# PT08.net
KiCad netlist of a schematic drawn in EAGLE
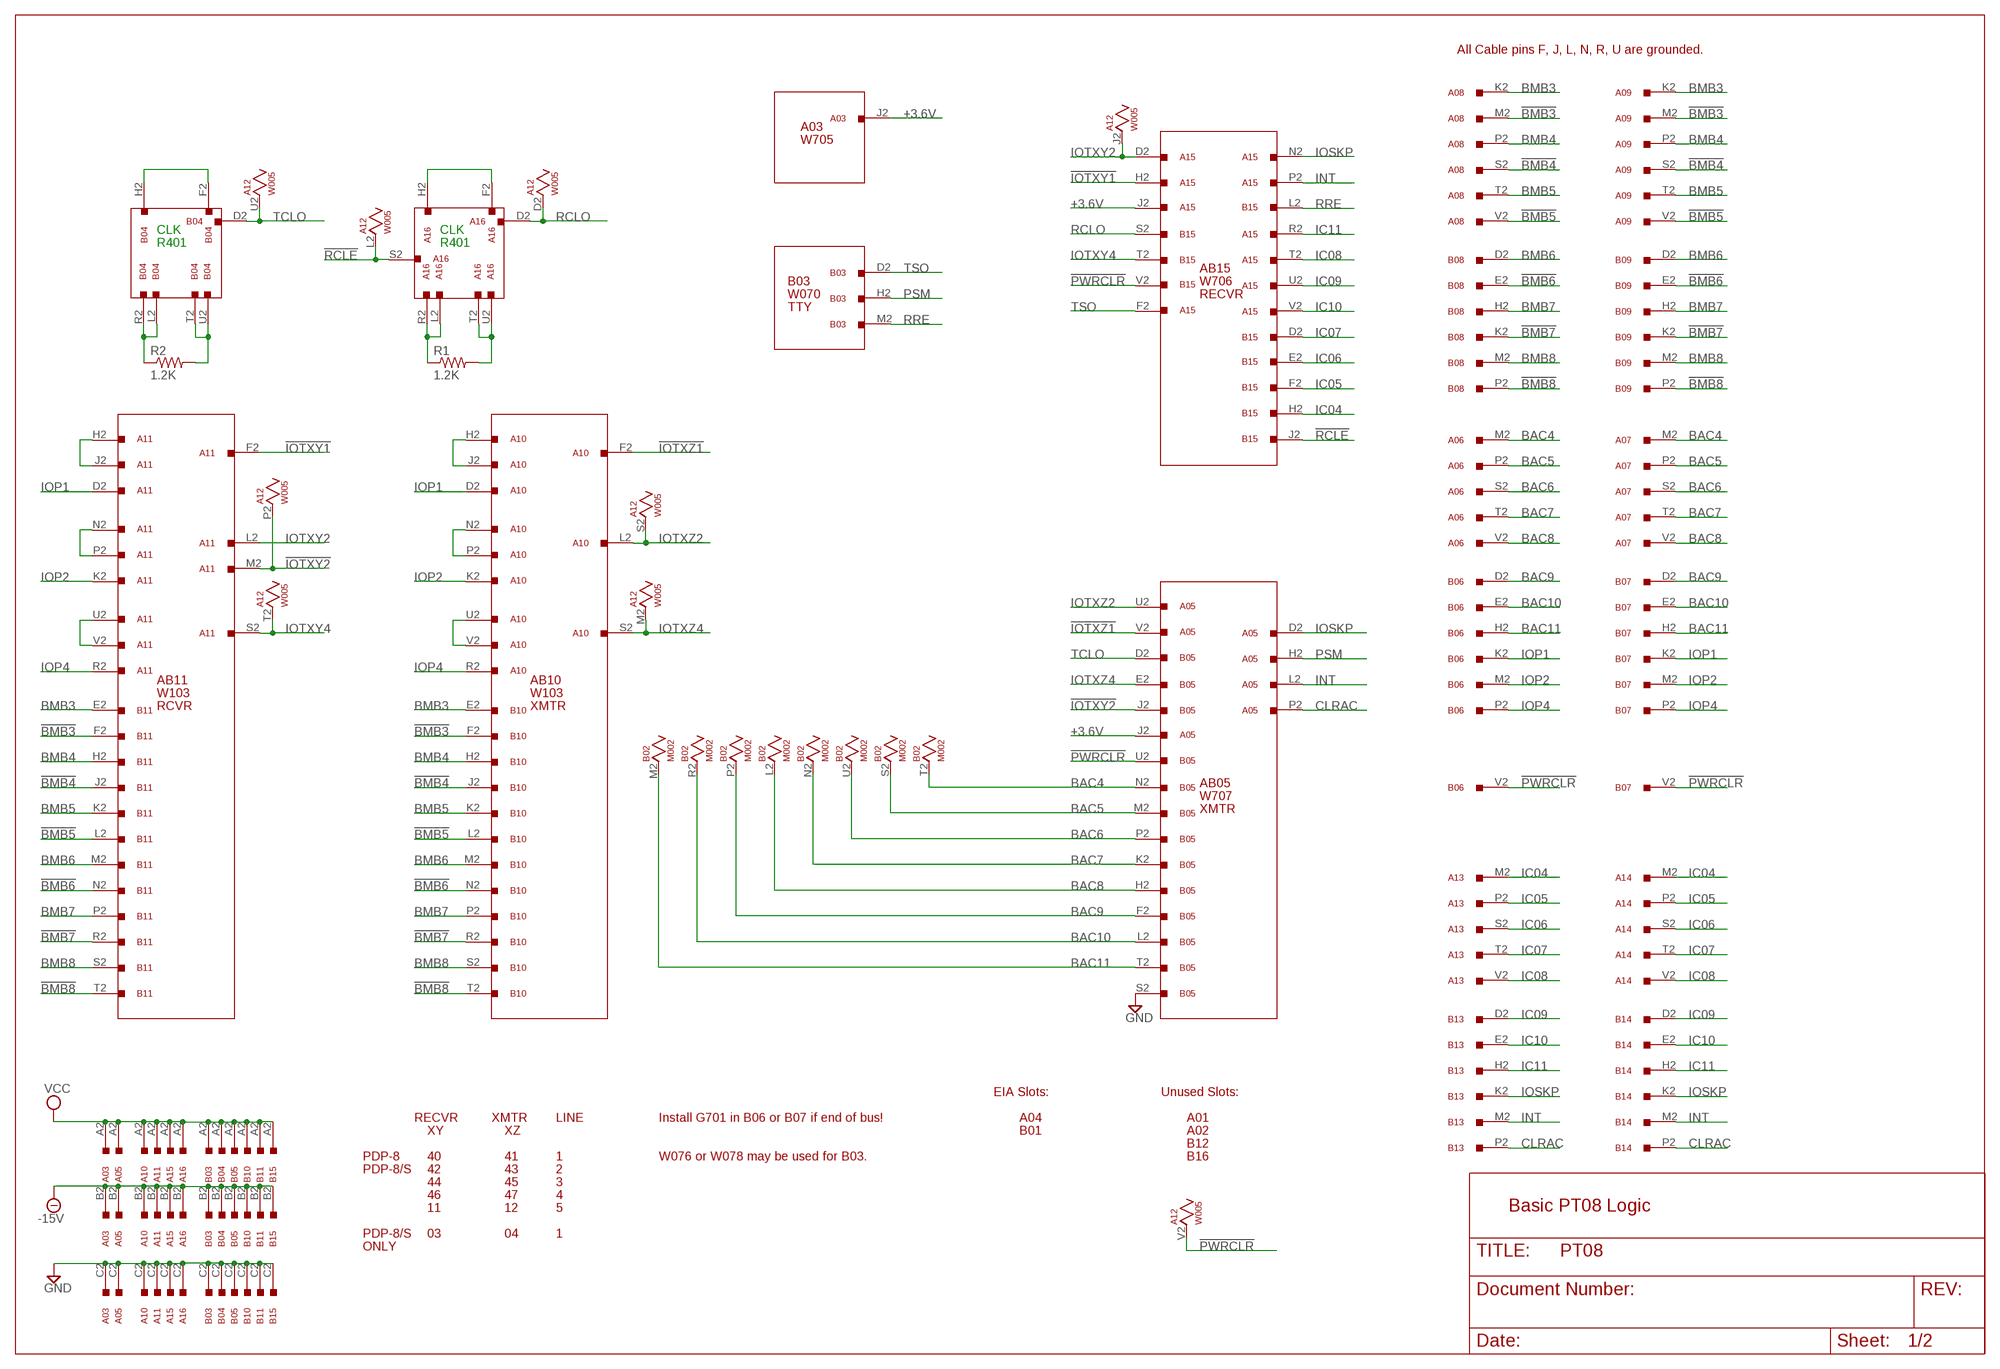
[diagram p0: schematic, sheet 1]
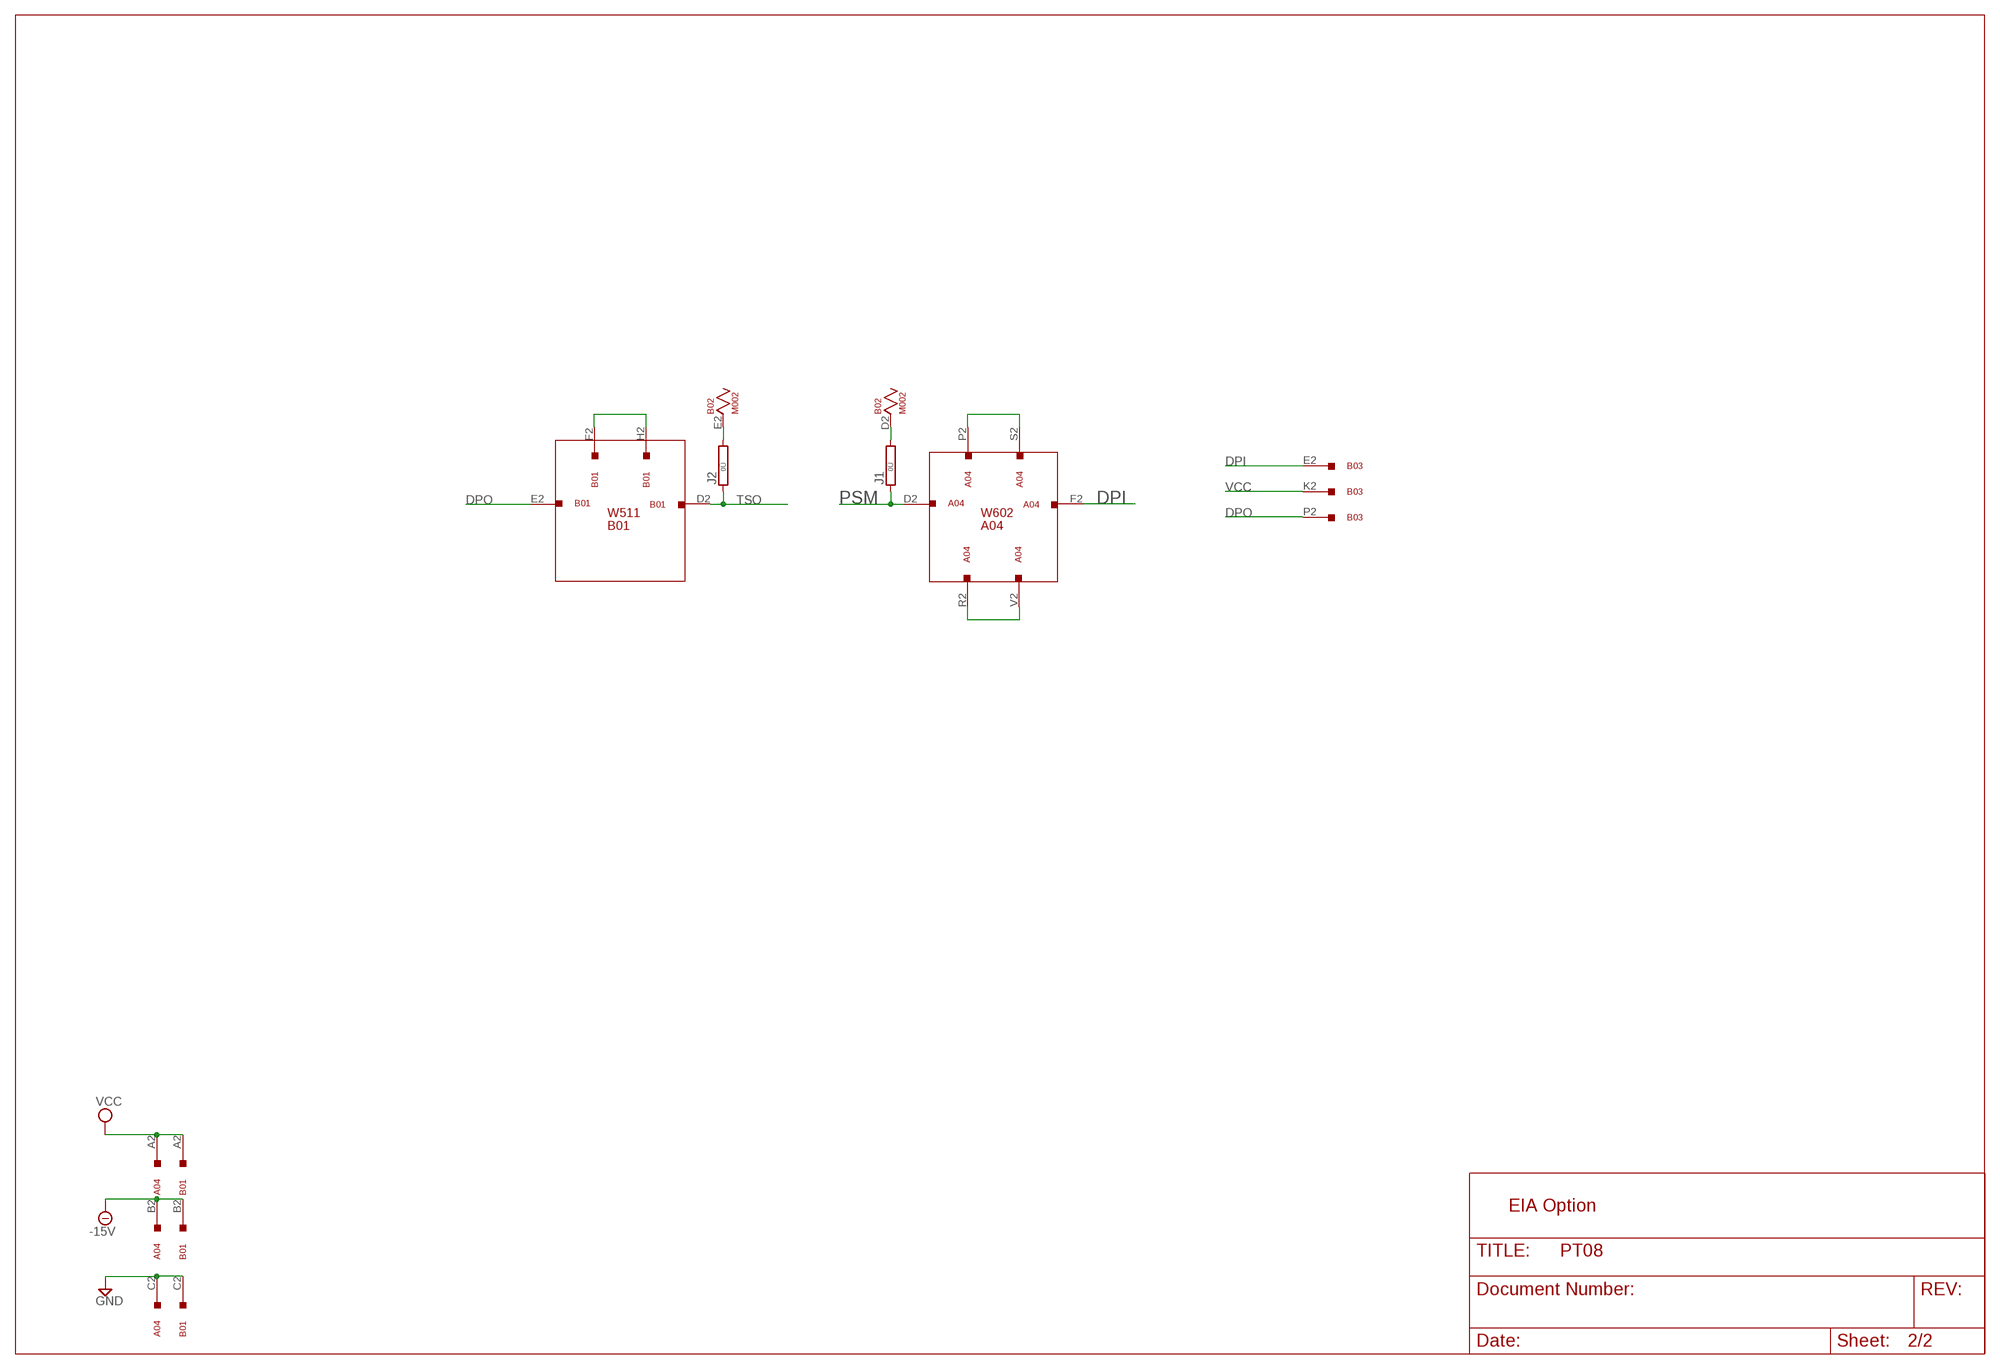
[diagram p1: schematic, sheet 2]

(export (version "E")
  (design (tool "Eeschema 10.0.6"))
  (components
    (comp (ref "A01")
      (value "H807")
      (footprint "eagle-import:H807")
      (libsource (lib "eagle-import") (part "H807"))
    )
    (comp (ref "A02")
      (value "H807")
      (footprint "eagle-import:H807")
      (libsource (lib "eagle-import") (part "H807"))
    )
    (comp (ref "A03")
      (value "W705")
      (footprint "eagle-import:H807")
      (libsource (lib "eagle-import") (part "W023"))
    )
    (comp (ref "A05")
      (value "W707")
      (footprint "eagle-import:H807")
      (libsource (lib "eagle-import") (part "W023"))
    )
    (comp (ref "A06")
      (value "W011")
      (footprint "eagle-import:H807")
      (libsource (lib "eagle-import") (part "W011"))
    )
    (comp (ref "A07")
      (value "W011")
      (footprint "eagle-import:H807")
      (libsource (lib "eagle-import") (part "W011"))
    )
    (comp (ref "A08")
      (value "W011")
      (footprint "eagle-import:H807")
      (libsource (lib "eagle-import") (part "W011"))
    )
    (comp (ref "A09")
      (value "W011")
      (footprint "eagle-import:H807")
      (libsource (lib "eagle-import") (part "W011"))
    )
    (comp (ref "A10")
      (value "W103")
      (footprint "eagle-import:H807")
      (libsource (lib "eagle-import") (part "W023"))
    )
    (comp (ref "A11")
      (value "W103")
      (footprint "eagle-import:H807")
      (libsource (lib "eagle-import") (part "W023"))
    )
    (comp (ref "A12")
      (value "W005")
      (footprint "eagle-import:H807")
      (libsource (lib "eagle-import") (part "W005"))
    )
    (comp (ref "A13")
      (value "W011")
      (footprint "eagle-import:H807")
      (libsource (lib "eagle-import") (part "W011"))
    )
    (comp (ref "A14")
      (value "W011")
      (footprint "eagle-import:H807")
      (libsource (lib "eagle-import") (part "W011"))
    )
    (comp (ref "A15")
      (value "W706")
      (footprint "eagle-import:H807")
      (libsource (lib "eagle-import") (part "W023"))
    )
    (comp (ref "A16")
      (value "R401")
      (footprint "eagle-import:H807")
      (libsource (lib "eagle-import") (part "W023"))
    )
    (comp (ref "B02")
      (value "M002")
      (footprint "eagle-import:H807")
      (libsource (lib "eagle-import") (part "M002"))
    )
    (comp (ref "B03")
      (value "W076")
      (footprint "eagle-import:H807")
      (libsource (lib "eagle-import") (part "W023"))
    )
    (comp (ref "B04")
      (value "R401")
      (footprint "eagle-import:H807")
      (libsource (lib "eagle-import") (part "W023"))
    )
    (comp (ref "B05")
      (value "W707")
      (footprint "eagle-import:H807")
      (libsource (lib "eagle-import") (part "W023"))
    )
    (comp (ref "B06")
      (value "W011")
      (footprint "eagle-import:H807")
      (libsource (lib "eagle-import") (part "W011"))
    )
    (comp (ref "B07")
      (value "W011")
      (footprint "eagle-import:H807")
      (libsource (lib "eagle-import") (part "W011"))
    )
    (comp (ref "B08")
      (value "W011")
      (footprint "eagle-import:H807")
      (libsource (lib "eagle-import") (part "W011"))
    )
    (comp (ref "B09")
      (value "W011")
      (footprint "eagle-import:H807")
      (libsource (lib "eagle-import") (part "W011"))
    )
    (comp (ref "B10")
      (value "W103")
      (footprint "eagle-import:H807")
      (libsource (lib "eagle-import") (part "W023"))
    )
    (comp (ref "B11")
      (value "W103")
      (footprint "eagle-import:H807")
      (libsource (lib "eagle-import") (part "W023"))
    )
    (comp (ref "B12")
      (value "H807")
      (footprint "eagle-import:H807")
      (libsource (lib "eagle-import") (part "H807"))
    )
    (comp (ref "B13")
      (value "W011")
      (footprint "eagle-import:H807")
      (libsource (lib "eagle-import") (part "W011"))
    )
    (comp (ref "B14")
      (value "W011")
      (footprint "eagle-import:H807")
      (libsource (lib "eagle-import") (part "W011"))
    )
    (comp (ref "B15")
      (value "W706")
      (footprint "eagle-import:H807")
      (libsource (lib "eagle-import") (part "W023"))
    )
    (comp (ref "B16")
      (value "H807")
      (footprint "eagle-import:H807")
      (libsource (lib "eagle-import") (part "H807"))
    )
    (comp (ref "R1")
      (value "1.2K")
      (footprint "eagle-import:0207_10")
      (libsource (lib "eagle-import") (part "R-US_0207/10"))
    )
    (comp (ref "R2")
      (value "1.2K")
      (footprint "eagle-import:0207_10")
      (libsource (lib "eagle-import") (part "R-US_0207/10"))
    )
    (comp (ref "A04")
      (value "W602")
      (footprint "eagle-import:H807")
      (libsource (lib "eagle-import") (part "W023"))
    )
    (comp (ref "B01")
      (value "W511")
      (footprint "eagle-import:H807")
      (libsource (lib "eagle-import") (part "W023"))
    )
    (comp (ref "J1")
      (value "0R")
      (footprint "eagle-import:0R_10")
      (libsource (lib "eagle-import") (part "0R"))
    )
    (comp (ref "J2")
      (value "0R")
      (footprint "eagle-import:0R_10")
      (libsource (lib "eagle-import") (part "0R"))
    )
  )
  (nets
    (net (code "1") (name "+3.6V") (class "Default")
      (node (ref "A03") (pin "J2") (pinfunction "P$2_J2") (pintype "bidirectional"))
      (node (ref "A05") (pin "J2") (pinfunction "P$2_J2") (pintype "bidirectional"))
      (node (ref "A15") (pin "J2") (pinfunction "P$2_J2") (pintype "bidirectional"))
    )
    (net (code "2") (name "-15V") (class "Default")
      (node (ref "A03") (pin "B2") (pinfunction "P$2_B2") (pintype "bidirectional"))
      (node (ref "A04") (pin "B2") (pinfunction "P$2_B2") (pintype "bidirectional"))
      (node (ref "A05") (pin "B2") (pinfunction "P$2_B2") (pintype "bidirectional"))
      (node (ref "A10") (pin "B2") (pinfunction "P$2_B2") (pintype "bidirectional"))
      (node (ref "A11") (pin "B2") (pinfunction "P$2_B2") (pintype "bidirectional"))
      (node (ref "A15") (pin "B2") (pinfunction "P$2_B2") (pintype "bidirectional"))
      (node (ref "A16") (pin "B2") (pinfunction "P$2_B2") (pintype "bidirectional"))
      (node (ref "B01") (pin "B2") (pinfunction "P$2_B2") (pintype "bidirectional"))
      (node (ref "B03") (pin "B2") (pinfunction "P$2_B2") (pintype "bidirectional"))
      (node (ref "B04") (pin "B2") (pinfunction "P$2_B2") (pintype "bidirectional"))
      (node (ref "B05") (pin "B2") (pinfunction "P$2_B2") (pintype "bidirectional"))
      (node (ref "B10") (pin "B2") (pinfunction "P$2_B2") (pintype "bidirectional"))
      (node (ref "B11") (pin "B2") (pinfunction "P$2_B2") (pintype "bidirectional"))
      (node (ref "B15") (pin "B2") (pinfunction "P$2_B2") (pintype "bidirectional"))
    )
    (net (code "3") (name "BAC4") (class "Default")
      (node (ref "A06") (pin "M2") (pinfunction "P$2_M2") (pintype "bidirectional"))
      (node (ref "A07") (pin "M2") (pinfunction "P$2_M2") (pintype "bidirectional"))
      (node (ref "B02") (pin "T2") (pinfunction "P$1_T2") (pintype "passive"))
      (node (ref "B05") (pin "N2") (pinfunction "P$2_N2") (pintype "bidirectional"))
    )
    (net (code "4") (name "BAC5") (class "Default")
      (node (ref "A06") (pin "P2") (pinfunction "P$2_P2") (pintype "bidirectional"))
      (node (ref "A07") (pin "P2") (pinfunction "P$2_P2") (pintype "bidirectional"))
      (node (ref "B02") (pin "S2") (pinfunction "P$1_S2") (pintype "passive"))
      (node (ref "B05") (pin "M2") (pinfunction "P$2_M2") (pintype "bidirectional"))
    )
    (net (code "5") (name "BAC6") (class "Default")
      (node (ref "A06") (pin "S2") (pinfunction "P$2_S2") (pintype "bidirectional"))
      (node (ref "A07") (pin "S2") (pinfunction "P$2_S2") (pintype "bidirectional"))
      (node (ref "B02") (pin "U2") (pinfunction "P$1_U2") (pintype "passive"))
      (node (ref "B05") (pin "P2") (pinfunction "P$2_P2") (pintype "bidirectional"))
    )
    (net (code "6") (name "BAC7") (class "Default")
      (node (ref "A06") (pin "T2") (pinfunction "P$2_T2") (pintype "bidirectional"))
      (node (ref "A07") (pin "T2") (pinfunction "P$2_T2") (pintype "bidirectional"))
      (node (ref "B02") (pin "N2") (pinfunction "P$1_N2") (pintype "passive"))
      (node (ref "B05") (pin "K2") (pinfunction "P$2_K2") (pintype "bidirectional"))
    )
    (net (code "7") (name "BAC8") (class "Default")
      (node (ref "A06") (pin "V2") (pinfunction "P$2_V2") (pintype "bidirectional"))
      (node (ref "A07") (pin "V2") (pinfunction "P$2_V2") (pintype "bidirectional"))
      (node (ref "B02") (pin "L2") (pinfunction "P$1_L2") (pintype "passive"))
      (node (ref "B05") (pin "H2") (pinfunction "P$2_H2") (pintype "bidirectional"))
    )
    (net (code "8") (name "BAC9") (class "Default")
      (node (ref "B02") (pin "P2") (pinfunction "P$1_P2") (pintype "passive"))
      (node (ref "B05") (pin "F2") (pinfunction "P$2_F2") (pintype "bidirectional"))
      (node (ref "B06") (pin "D2") (pinfunction "P$2_D2") (pintype "bidirectional"))
      (node (ref "B07") (pin "D2") (pinfunction "P$2_D2") (pintype "bidirectional"))
    )
    (net (code "9") (name "BAC10") (class "Default")
      (node (ref "B02") (pin "R2") (pinfunction "P$1_R2") (pintype "passive"))
      (node (ref "B05") (pin "L2") (pinfunction "P$2_L2") (pintype "bidirectional"))
      (node (ref "B06") (pin "E2") (pinfunction "P$2_E2") (pintype "bidirectional"))
      (node (ref "B07") (pin "E2") (pinfunction "P$2_E2") (pintype "bidirectional"))
    )
    (net (code "10") (name "BAC11") (class "Default")
      (node (ref "B02") (pin "M2") (pinfunction "P$1_M2") (pintype "passive"))
      (node (ref "B05") (pin "T2") (pinfunction "P$2_T2") (pintype "bidirectional"))
      (node (ref "B06") (pin "H2") (pinfunction "P$2_H2") (pintype "bidirectional"))
      (node (ref "B07") (pin "H2") (pinfunction "P$2_H2") (pintype "bidirectional"))
    )
    (net (code "11") (name "BMB3") (class "Default")
      (node (ref "A08") (pin "K2") (pinfunction "P$2_K2") (pintype "bidirectional"))
      (node (ref "A09") (pin "K2") (pinfunction "P$2_K2") (pintype "bidirectional"))
      (node (ref "B10") (pin "E2") (pinfunction "P$2_E2") (pintype "bidirectional"))
      (node (ref "B11") (pin "E2") (pinfunction "P$2_E2") (pintype "bidirectional"))
    )
    (net (code "12") (name "BMB4") (class "Default")
      (node (ref "A08") (pin "P2") (pinfunction "P$2_P2") (pintype "bidirectional"))
      (node (ref "A09") (pin "P2") (pinfunction "P$2_P2") (pintype "bidirectional"))
      (node (ref "B10") (pin "H2") (pinfunction "P$2_H2") (pintype "bidirectional"))
      (node (ref "B11") (pin "H2") (pinfunction "P$2_H2") (pintype "bidirectional"))
    )
    (net (code "13") (name "BMB5") (class "Default")
      (node (ref "A08") (pin "T2") (pinfunction "P$2_T2") (pintype "bidirectional"))
      (node (ref "A09") (pin "T2") (pinfunction "P$2_T2") (pintype "bidirectional"))
      (node (ref "B10") (pin "K2") (pinfunction "P$2_K2") (pintype "bidirectional"))
      (node (ref "B11") (pin "K2") (pinfunction "P$2_K2") (pintype "bidirectional"))
    )
    (net (code "14") (name "BMB6") (class "Default")
      (node (ref "B08") (pin "D2") (pinfunction "P$2_D2") (pintype "bidirectional"))
      (node (ref "B09") (pin "D2") (pinfunction "P$2_D2") (pintype "bidirectional"))
      (node (ref "B10") (pin "M2") (pinfunction "P$2_M2") (pintype "bidirectional"))
      (node (ref "B11") (pin "M2") (pinfunction "P$2_M2") (pintype "bidirectional"))
    )
    (net (code "15") (name "BMB7") (class "Default")
      (node (ref "B08") (pin "H2") (pinfunction "P$2_H2") (pintype "bidirectional"))
      (node (ref "B09") (pin "H2") (pinfunction "P$2_H2") (pintype "bidirectional"))
      (node (ref "B10") (pin "P2") (pinfunction "P$2_P2") (pintype "bidirectional"))
      (node (ref "B11") (pin "P2") (pinfunction "P$2_P2") (pintype "bidirectional"))
    )
    (net (code "16") (name "BMB8") (class "Default")
      (node (ref "B08") (pin "M2") (pinfunction "P$2_M2") (pintype "bidirectional"))
      (node (ref "B09") (pin "M2") (pinfunction "P$2_M2") (pintype "bidirectional"))
      (node (ref "B10") (pin "S2") (pinfunction "P$2_S2") (pintype "bidirectional"))
      (node (ref "B11") (pin "S2") (pinfunction "P$2_S2") (pintype "bidirectional"))
    )
    (net (code "17") (name "CLRAC") (class "Default")
      (node (ref "A05") (pin "P2") (pinfunction "P$2_P2") (pintype "bidirectional"))
      (node (ref "B13") (pin "P2") (pinfunction "P$2_P2") (pintype "bidirectional"))
      (node (ref "B14") (pin "P2") (pinfunction "P$2_P2") (pintype "bidirectional"))
    )
    (net (code "18") (name "DPI") (class "Default")
      (node (ref "A04") (pin "F2") (pinfunction "P$2_F2") (pintype "bidirectional"))
      (node (ref "B03") (pin "E2") (pinfunction "P$2_E2") (pintype "bidirectional"))
    )
    (net (code "19") (name "DPO") (class "Default")
      (node (ref "B01") (pin "E2") (pinfunction "P$2_E2") (pintype "bidirectional"))
      (node (ref "B03") (pin "P2") (pinfunction "P$2_P2") (pintype "bidirectional"))
    )
    (net (code "20") (name "GND") (class "Default")
      (node (ref "A03") (pin "C2") (pinfunction "P$2_C2") (pintype "bidirectional"))
      (node (ref "A04") (pin "C2") (pinfunction "P$2_C2") (pintype "bidirectional"))
      (node (ref "A05") (pin "C2") (pinfunction "P$2_C2") (pintype "bidirectional"))
      (node (ref "A10") (pin "C2") (pinfunction "P$2_C2") (pintype "bidirectional"))
      (node (ref "A11") (pin "C2") (pinfunction "P$2_C2") (pintype "bidirectional"))
      (node (ref "A15") (pin "C2") (pinfunction "P$2_C2") (pintype "bidirectional"))
      (node (ref "A16") (pin "C2") (pinfunction "P$2_C2") (pintype "bidirectional"))
      (node (ref "B01") (pin "C2") (pinfunction "P$2_C2") (pintype "bidirectional"))
      (node (ref "B03") (pin "C2") (pinfunction "P$2_C2") (pintype "bidirectional"))
      (node (ref "B04") (pin "C2") (pinfunction "P$2_C2") (pintype "bidirectional"))
      (node (ref "B05") (pin "C2") (pinfunction "P$2_C2") (pintype "bidirectional"))
      (node (ref "B05") (pin "S2") (pinfunction "P$2_S2") (pintype "bidirectional"))
      (node (ref "B10") (pin "C2") (pinfunction "P$2_C2") (pintype "bidirectional"))
      (node (ref "B11") (pin "C2") (pinfunction "P$2_C2") (pintype "bidirectional"))
      (node (ref "B15") (pin "C2") (pinfunction "P$2_C2") (pintype "bidirectional"))
    )
    (net (code "21") (name "IC04") (class "Default")
      (node (ref "A13") (pin "M2") (pinfunction "P$2_M2") (pintype "bidirectional"))
      (node (ref "A14") (pin "M2") (pinfunction "P$2_M2") (pintype "bidirectional"))
      (node (ref "B15") (pin "H2") (pinfunction "P$2_H2") (pintype "bidirectional"))
    )
    (net (code "22") (name "IC05") (class "Default")
      (node (ref "A13") (pin "P2") (pinfunction "P$2_P2") (pintype "bidirectional"))
      (node (ref "A14") (pin "P2") (pinfunction "P$2_P2") (pintype "bidirectional"))
      (node (ref "B15") (pin "F2") (pinfunction "P$2_F2") (pintype "bidirectional"))
    )
    (net (code "23") (name "IC06") (class "Default")
      (node (ref "A13") (pin "S2") (pinfunction "P$2_S2") (pintype "bidirectional"))
      (node (ref "A14") (pin "S2") (pinfunction "P$2_S2") (pintype "bidirectional"))
      (node (ref "B15") (pin "E2") (pinfunction "P$2_E2") (pintype "bidirectional"))
    )
    (net (code "24") (name "IC07") (class "Default")
      (node (ref "A13") (pin "T2") (pinfunction "P$2_T2") (pintype "bidirectional"))
      (node (ref "A14") (pin "T2") (pinfunction "P$2_T2") (pintype "bidirectional"))
      (node (ref "B15") (pin "D2") (pinfunction "P$2_D2") (pintype "bidirectional"))
    )
    (net (code "25") (name "IC08") (class "Default")
      (node (ref "A13") (pin "V2") (pinfunction "P$2_V2") (pintype "bidirectional"))
      (node (ref "A14") (pin "V2") (pinfunction "P$2_V2") (pintype "bidirectional"))
      (node (ref "A15") (pin "T2") (pinfunction "P$2_T2") (pintype "bidirectional"))
    )
    (net (code "26") (name "IC09") (class "Default")
      (node (ref "A15") (pin "U2") (pinfunction "P$2_U2") (pintype "bidirectional"))
      (node (ref "B13") (pin "D2") (pinfunction "P$2_D2") (pintype "bidirectional"))
      (node (ref "B14") (pin "D2") (pinfunction "P$2_D2") (pintype "bidirectional"))
    )
    (net (code "27") (name "IC10") (class "Default")
      (node (ref "A15") (pin "V2") (pinfunction "P$2_V2") (pintype "bidirectional"))
      (node (ref "B13") (pin "E2") (pinfunction "P$2_E2") (pintype "bidirectional"))
      (node (ref "B14") (pin "E2") (pinfunction "P$2_E2") (pintype "bidirectional"))
    )
    (net (code "28") (name "IC11") (class "Default")
      (node (ref "A15") (pin "R2") (pinfunction "P$2_R2") (pintype "bidirectional"))
      (node (ref "B13") (pin "H2") (pinfunction "P$2_H2") (pintype "bidirectional"))
      (node (ref "B14") (pin "H2") (pinfunction "P$2_H2") (pintype "bidirectional"))
    )
    (net (code "29") (name "INT") (class "Default")
      (node (ref "A05") (pin "L2") (pinfunction "P$2_L2") (pintype "bidirectional"))
      (node (ref "A15") (pin "P2") (pinfunction "P$2_P2") (pintype "bidirectional"))
      (node (ref "B13") (pin "M2") (pinfunction "P$2_M2") (pintype "bidirectional"))
      (node (ref "B14") (pin "M2") (pinfunction "P$2_M2") (pintype "bidirectional"))
    )
    (net (code "30") (name "IOP1") (class "Default")
      (node (ref "A10") (pin "D2") (pinfunction "P$2_D2") (pintype "bidirectional"))
      (node (ref "A11") (pin "D2") (pinfunction "P$2_D2") (pintype "bidirectional"))
      (node (ref "B06") (pin "K2") (pinfunction "P$2_K2") (pintype "bidirectional"))
      (node (ref "B07") (pin "K2") (pinfunction "P$2_K2") (pintype "bidirectional"))
    )
    (net (code "31") (name "IOP2") (class "Default")
      (node (ref "A10") (pin "K2") (pinfunction "P$2_K2") (pintype "bidirectional"))
      (node (ref "A11") (pin "K2") (pinfunction "P$2_K2") (pintype "bidirectional"))
      (node (ref "B06") (pin "M2") (pinfunction "P$2_M2") (pintype "bidirectional"))
      (node (ref "B07") (pin "M2") (pinfunction "P$2_M2") (pintype "bidirectional"))
    )
    (net (code "32") (name "IOP4") (class "Default")
      (node (ref "A10") (pin "R2") (pinfunction "P$2_R2") (pintype "bidirectional"))
      (node (ref "A11") (pin "R2") (pinfunction "P$2_R2") (pintype "bidirectional"))
      (node (ref "B06") (pin "P2") (pinfunction "P$2_P2") (pintype "bidirectional"))
      (node (ref "B07") (pin "P2") (pinfunction "P$2_P2") (pintype "bidirectional"))
    )
    (net (code "33") (name "IOSKP") (class "Default")
      (node (ref "A05") (pin "D2") (pinfunction "P$2_D2") (pintype "bidirectional"))
      (node (ref "A15") (pin "N2") (pinfunction "P$2_N2") (pintype "bidirectional"))
      (node (ref "B13") (pin "K2") (pinfunction "P$2_K2") (pintype "bidirectional"))
      (node (ref "B14") (pin "K2") (pinfunction "P$2_K2") (pintype "bidirectional"))
    )
    (net (code "34") (name "IOTXY2") (class "Default")
      (node (ref "A11") (pin "L2") (pinfunction "P$2_L2") (pintype "bidirectional"))
      (node (ref "A12") (pin "J2") (pinfunction "P$1_J2") (pintype "passive"))
      (node (ref "A15") (pin "D2") (pinfunction "P$2_D2") (pintype "bidirectional"))
    )
    (net (code "35") (name "IOTXY4") (class "Default")
      (node (ref "A11") (pin "S2") (pinfunction "P$2_S2") (pintype "bidirectional"))
      (node (ref "A12") (pin "T2") (pinfunction "P$1_T2") (pintype "passive"))
      (node (ref "B15") (pin "T2") (pinfunction "P$2_T2") (pintype "bidirectional"))
    )
    (net (code "36") (name "IOTXZ2") (class "Default")
      (node (ref "A05") (pin "U2") (pinfunction "P$2_U2") (pintype "bidirectional"))
      (node (ref "A10") (pin "L2") (pinfunction "P$2_L2") (pintype "bidirectional"))
      (node (ref "A12") (pin "S2") (pinfunction "P$1_S2") (pintype "passive"))
    )
    (net (code "37") (name "IOTXZ4") (class "Default")
      (node (ref "A10") (pin "S2") (pinfunction "P$2_S2") (pintype "bidirectional"))
      (node (ref "A12") (pin "M2") (pinfunction "P$1_M2") (pintype "passive"))
      (node (ref "B05") (pin "E2") (pinfunction "P$2_E2") (pintype "bidirectional"))
    )
    (net (code "38") (name "Net-(A04M-P$2)") (class "Default")
      (node (ref "A04") (pin "P2") (pinfunction "P$2_P2") (pintype "bidirectional"))
      (node (ref "A04") (pin "S2") (pinfunction "P$2_S2") (pintype "bidirectional"))
    )
    (net (code "39") (name "Net-(A04N-P$2)") (class "Default")
      (node (ref "A04") (pin "R2") (pinfunction "P$2_R2") (pintype "bidirectional"))
      (node (ref "A04") (pin "V2") (pinfunction "P$2_V2") (pintype "bidirectional"))
    )
    (net (code "40") (name "Net-(A10G-P$2)") (class "Default")
      (node (ref "A10") (pin "H2") (pinfunction "P$2_H2") (pintype "bidirectional"))
      (node (ref "A10") (pin "J2") (pinfunction "P$2_J2") (pintype "bidirectional"))
    )
    (net (code "41") (name "Net-(A10L-P$2)") (class "Default")
      (node (ref "A10") (pin "N2") (pinfunction "P$2_N2") (pintype "bidirectional"))
      (node (ref "A10") (pin "P2") (pinfunction "P$2_P2") (pintype "bidirectional"))
    )
    (net (code "42") (name "Net-(A10Q-P$2)") (class "Default")
      (node (ref "A10") (pin "U2") (pinfunction "P$2_U2") (pintype "bidirectional"))
      (node (ref "A10") (pin "V2") (pinfunction "P$2_V2") (pintype "bidirectional"))
    )
    (net (code "43") (name "Net-(A11G-P$2)") (class "Default")
      (node (ref "A11") (pin "H2") (pinfunction "P$2_H2") (pintype "bidirectional"))
      (node (ref "A11") (pin "J2") (pinfunction "P$2_J2") (pintype "bidirectional"))
    )
    (net (code "44") (name "Net-(A11L-P$2)") (class "Default")
      (node (ref "A11") (pin "N2") (pinfunction "P$2_N2") (pintype "bidirectional"))
      (node (ref "A11") (pin "P2") (pinfunction "P$2_P2") (pintype "bidirectional"))
    )
    (net (code "45") (name "Net-(A11Q-P$2)") (class "Default")
      (node (ref "A11") (pin "U2") (pinfunction "P$2_U2") (pintype "bidirectional"))
      (node (ref "A11") (pin "V2") (pinfunction "P$2_V2") (pintype "bidirectional"))
    )
    (net (code "46") (name "Net-(A16F-P$2)") (class "Default")
      (node (ref "A16") (pin "F2") (pinfunction "P$2_F2") (pintype "bidirectional"))
      (node (ref "A16") (pin "H2") (pinfunction "P$2_H2") (pintype "bidirectional"))
    )
    (net (code "47") (name "Net-(A16J-P$2)") (class "Default")
      (node (ref "A16") (pin "L2") (pinfunction "P$2_L2") (pintype "bidirectional"))
      (node (ref "A16") (pin "R2") (pinfunction "P$2_R2") (pintype "bidirectional"))
      (node (ref "R1") (pin "1") (pinfunction "1_1") (pintype "passive"))
    )
    (net (code "48") (name "Net-(A16P-P$2)") (class "Default")
      (node (ref "A16") (pin "T2") (pinfunction "P$2_T2") (pintype "bidirectional"))
      (node (ref "A16") (pin "U2") (pinfunction "P$2_U2") (pintype "bidirectional"))
      (node (ref "R1") (pin "2") (pinfunction "2_2") (pintype "passive"))
    )
    (net (code "49") (name "Net-(B01F-P$2)") (class "Default")
      (node (ref "B01") (pin "F2") (pinfunction "P$2_F2") (pintype "bidirectional"))
      (node (ref "B01") (pin "H2") (pinfunction "P$2_H2") (pintype "bidirectional"))
    )
    (net (code "50") (name "Net-(B02A-P$1)") (class "Default")
      (node (ref "B02") (pin "D2") (pinfunction "P$1_D2") (pintype "passive"))
      (node (ref "J1") (pin "2") (pinfunction "2_2") (pintype "passive"))
    )
    (net (code "51") (name "Net-(B02B-P$1)") (class "Default")
      (node (ref "B02") (pin "E2") (pinfunction "P$1_E2") (pintype "passive"))
      (node (ref "J2") (pin "2") (pinfunction "2_2") (pintype "passive"))
    )
    (net (code "52") (name "Net-(B04F-P$2)") (class "Default")
      (node (ref "B04") (pin "F2") (pinfunction "P$2_F2") (pintype "bidirectional"))
      (node (ref "B04") (pin "H2") (pinfunction "P$2_H2") (pintype "bidirectional"))
    )
    (net (code "53") (name "Net-(B04J-P$2)") (class "Default")
      (node (ref "B04") (pin "L2") (pinfunction "P$2_L2") (pintype "bidirectional"))
      (node (ref "B04") (pin "R2") (pinfunction "P$2_R2") (pintype "bidirectional"))
      (node (ref "R2") (pin "1") (pinfunction "1_1") (pintype "passive"))
    )
    (net (code "54") (name "Net-(B04P-P$2)") (class "Default")
      (node (ref "B04") (pin "T2") (pinfunction "P$2_T2") (pintype "bidirectional"))
      (node (ref "B04") (pin "U2") (pinfunction "P$2_U2") (pintype "bidirectional"))
      (node (ref "R2") (pin "2") (pinfunction "2_2") (pintype "passive"))
    )
    (net (code "55") (name "PSM") (class "Default")
      (node (ref "A04") (pin "D2") (pinfunction "P$2_D2") (pintype "bidirectional"))
      (node (ref "A05") (pin "H2") (pinfunction "P$2_H2") (pintype "bidirectional"))
      (node (ref "B03") (pin "H2") (pinfunction "P$2_H2") (pintype "bidirectional"))
      (node (ref "J1") (pin "1") (pinfunction "1_1") (pintype "passive"))
    )
    (net (code "56") (name "RCLO") (class "Default")
      (node (ref "A12") (pin "D2") (pinfunction "P$1_D2") (pintype "passive"))
      (node (ref "A16") (pin "D2") (pinfunction "P$2_D2") (pintype "bidirectional"))
      (node (ref "B15") (pin "S2") (pinfunction "P$2_S2") (pintype "bidirectional"))
    )
    (net (code "57") (name "RRE") (class "Default")
      (node (ref "B03") (pin "M2") (pinfunction "P$2_M2") (pintype "bidirectional"))
      (node (ref "B15") (pin "L2") (pinfunction "P$2_L2") (pintype "bidirectional"))
    )
    (net (code "58") (name "TCLO") (class "Default")
      (node (ref "A12") (pin "U2") (pinfunction "P$1_U2") (pintype "passive"))
      (node (ref "B04") (pin "D2") (pinfunction "P$2_D2") (pintype "bidirectional"))
      (node (ref "B05") (pin "D2") (pinfunction "P$2_D2") (pintype "bidirectional"))
    )
    (net (code "59") (name "TSO") (class "Default")
      (node (ref "A15") (pin "F2") (pinfunction "P$2_F2") (pintype "bidirectional"))
      (node (ref "B01") (pin "D2") (pinfunction "P$2_D2") (pintype "bidirectional"))
      (node (ref "B03") (pin "D2") (pinfunction "P$2_D2") (pintype "bidirectional"))
      (node (ref "J2") (pin "1") (pinfunction "1_1") (pintype "passive"))
    )
    (net (code "60") (name "VCC") (class "Default")
      (node (ref "A03") (pin "A2") (pinfunction "P$2_A2") (pintype "bidirectional"))
      (node (ref "A04") (pin "A2") (pinfunction "P$2_A2") (pintype "bidirectional"))
      (node (ref "A05") (pin "A2") (pinfunction "P$2_A2") (pintype "bidirectional"))
      (node (ref "A10") (pin "A2") (pinfunction "P$2_A2") (pintype "bidirectional"))
      (node (ref "A11") (pin "A2") (pinfunction "P$2_A2") (pintype "bidirectional"))
      (node (ref "A15") (pin "A2") (pinfunction "P$2_A2") (pintype "bidirectional"))
      (node (ref "A16") (pin "A2") (pinfunction "P$2_A2") (pintype "bidirectional"))
      (node (ref "B01") (pin "A2") (pinfunction "P$2_A2") (pintype "bidirectional"))
      (node (ref "B03") (pin "A2") (pinfunction "P$2_A2") (pintype "bidirectional"))
      (node (ref "B03") (pin "K2") (pinfunction "P$2_K2") (pintype "bidirectional"))
      (node (ref "B04") (pin "A2") (pinfunction "P$2_A2") (pintype "bidirectional"))
      (node (ref "B05") (pin "A2") (pinfunction "P$2_A2") (pintype "bidirectional"))
      (node (ref "B10") (pin "A2") (pinfunction "P$2_A2") (pintype "bidirectional"))
      (node (ref "B11") (pin "A2") (pinfunction "P$2_A2") (pintype "bidirectional"))
      (node (ref "B15") (pin "A2") (pinfunction "P$2_A2") (pintype "bidirectional"))
    )
    (net (code "61") (name "~{BMB3}") (class "Default")
      (node (ref "A08") (pin "M2") (pinfunction "P$2_M2") (pintype "bidirectional"))
      (node (ref "A09") (pin "M2") (pinfunction "P$2_M2") (pintype "bidirectional"))
      (node (ref "B10") (pin "F2") (pinfunction "P$2_F2") (pintype "bidirectional"))
      (node (ref "B11") (pin "F2") (pinfunction "P$2_F2") (pintype "bidirectional"))
    )
    (net (code "62") (name "~{BMB4}") (class "Default")
      (node (ref "A08") (pin "S2") (pinfunction "P$2_S2") (pintype "bidirectional"))
      (node (ref "A09") (pin "S2") (pinfunction "P$2_S2") (pintype "bidirectional"))
      (node (ref "B10") (pin "J2") (pinfunction "P$2_J2") (pintype "bidirectional"))
      (node (ref "B11") (pin "J2") (pinfunction "P$2_J2") (pintype "bidirectional"))
    )
    (net (code "63") (name "~{BMB5}") (class "Default")
      (node (ref "A08") (pin "V2") (pinfunction "P$2_V2") (pintype "bidirectional"))
      (node (ref "A09") (pin "V2") (pinfunction "P$2_V2") (pintype "bidirectional"))
      (node (ref "B10") (pin "L2") (pinfunction "P$2_L2") (pintype "bidirectional"))
      (node (ref "B11") (pin "L2") (pinfunction "P$2_L2") (pintype "bidirectional"))
    )
    (net (code "64") (name "~{BMB6}") (class "Default")
      (node (ref "B08") (pin "E2") (pinfunction "P$2_E2") (pintype "bidirectional"))
      (node (ref "B09") (pin "E2") (pinfunction "P$2_E2") (pintype "bidirectional"))
      (node (ref "B10") (pin "N2") (pinfunction "P$2_N2") (pintype "bidirectional"))
      (node (ref "B11") (pin "N2") (pinfunction "P$2_N2") (pintype "bidirectional"))
    )
    (net (code "65") (name "~{BMB7}") (class "Default")
      (node (ref "B08") (pin "K2") (pinfunction "P$2_K2") (pintype "bidirectional"))
      (node (ref "B09") (pin "K2") (pinfunction "P$2_K2") (pintype "bidirectional"))
      (node (ref "B10") (pin "R2") (pinfunction "P$2_R2") (pintype "bidirectional"))
      (node (ref "B11") (pin "R2") (pinfunction "P$2_R2") (pintype "bidirectional"))
    )
    (net (code "66") (name "~{BMB8}") (class "Default")
      (node (ref "B08") (pin "P2") (pinfunction "P$2_P2") (pintype "bidirectional"))
      (node (ref "B09") (pin "P2") (pinfunction "P$2_P2") (pintype "bidirectional"))
      (node (ref "B10") (pin "T2") (pinfunction "P$2_T2") (pintype "bidirectional"))
      (node (ref "B11") (pin "T2") (pinfunction "P$2_T2") (pintype "bidirectional"))
    )
    (net (code "67") (name "~{IOTXY1}") (class "Default")
      (node (ref "A11") (pin "F2") (pinfunction "P$2_F2") (pintype "bidirectional"))
      (node (ref "A15") (pin "H2") (pinfunction "P$2_H2") (pintype "bidirectional"))
    )
    (net (code "68") (name "~{IOTXY2}") (class "Default")
      (node (ref "A11") (pin "M2") (pinfunction "P$2_M2") (pintype "bidirectional"))
      (node (ref "A12") (pin "P2") (pinfunction "P$1_P2") (pintype "passive"))
      (node (ref "B05") (pin "J2") (pinfunction "P$2_J2") (pintype "bidirectional"))
    )
    (net (code "69") (name "~{IOTXZ1}") (class "Default")
      (node (ref "A05") (pin "V2") (pinfunction "P$2_V2") (pintype "bidirectional"))
      (node (ref "A10") (pin "F2") (pinfunction "P$2_F2") (pintype "bidirectional"))
    )
    (net (code "70") (name "~{PWRCLR}") (class "Default")
      (node (ref "A12") (pin "V2") (pinfunction "P$1_V2") (pintype "passive"))
      (node (ref "B05") (pin "U2") (pinfunction "P$2_U2") (pintype "bidirectional"))
      (node (ref "B06") (pin "V2") (pinfunction "P$2_V2") (pintype "bidirectional"))
      (node (ref "B07") (pin "V2") (pinfunction "P$2_V2") (pintype "bidirectional"))
      (node (ref "B15") (pin "V2") (pinfunction "P$2_V2") (pintype "bidirectional"))
    )
    (net (code "71") (name "~{RCLE}") (class "Default")
      (node (ref "A12") (pin "L2") (pinfunction "P$1_L2") (pintype "passive"))
      (node (ref "A16") (pin "S2") (pinfunction "P$2_S2") (pintype "bidirectional"))
      (node (ref "B15") (pin "J2") (pinfunction "P$2_J2") (pintype "bidirectional"))
    )
  )
)
